# avr-isp-pdi-adapter.net
KiCad netlist of a schematic drawn in EAGLE
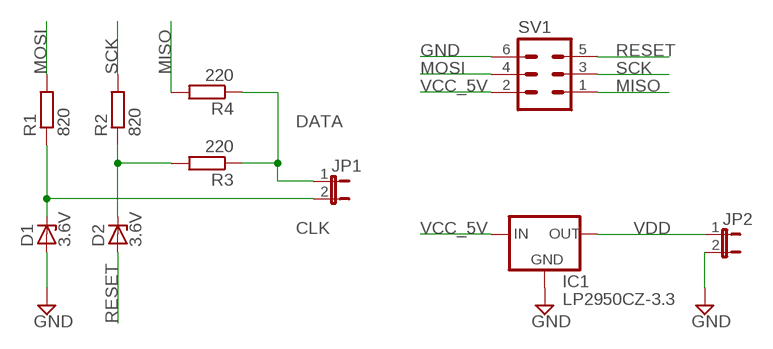
[diagram p0: schematic, sheet 1]

(export (version "E")
  (design (tool "Eeschema 10.0.6"))
  (components
    (comp (ref "D1")
      (value "3.6V")
      (footprint "eagle-import:DO34Z7")
      (libsource (lib "eagle-import") (part "ZENER-DIODEDO34-7"))
    )
    (comp (ref "D2")
      (value "3.6V")
      (footprint "eagle-import:DO34Z7")
      (libsource (lib "eagle-import") (part "ZENER-DIODEDO34-7"))
    )
    (comp (ref "IC1")
      (value "LP2950CZ-3.3")
      (footprint "eagle-import:TO92")
      (libsource (lib "eagle-import") (part "LP2950?CZ-3.3"))
    )
    (comp (ref "JP1")
      (value "JP1E")
      (footprint "eagle-import:JP1")
      (libsource (lib "eagle-import") (part "JP1E"))
    )
    (comp (ref "JP2")
      (value "JP1E")
      (footprint "eagle-import:JP1")
      (libsource (lib "eagle-import") (part "JP1E"))
    )
    (comp (ref "R1")
      (value "820")
      (footprint "eagle-import:0207_10")
      (libsource (lib "eagle-import") (part "R-EU_0207/10"))
    )
    (comp (ref "R2")
      (value "820")
      (footprint "eagle-import:0207_10")
      (libsource (lib "eagle-import") (part "R-EU_0207/10"))
    )
    (comp (ref "R3")
      (value "220")
      (footprint "eagle-import:0207_10")
      (libsource (lib "eagle-import") (part "R-EU_0207/10"))
    )
    (comp (ref "R4")
      (value "220")
      (footprint "eagle-import:0207_10")
      (libsource (lib "eagle-import") (part "R-EU_0207/10"))
    )
    (comp (ref "SV1")
      (value "MA03-2")
      (footprint "eagle-import:MA03-2")
      (libsource (lib "eagle-import") (part "MA03-2"))
    )
  )
  (nets
    (net (code "1") (name "/CLK") (class "Default")
      (node (ref "D1") (pin "C") (pinfunction "C_C") (pintype "passive"))
      (node (ref "JP1") (pin "2") (pinfunction "2_2") (pintype "passive"))
      (node (ref "R1") (pin "1") (pinfunction "1_1") (pintype "passive"))
    )
    (net (code "2") (name "/DATA") (class "Default")
      (node (ref "JP1") (pin "1") (pinfunction "1_1") (pintype "passive"))
      (node (ref "R3") (pin "1") (pinfunction "1_1") (pintype "passive"))
      (node (ref "R4") (pin "1") (pinfunction "1_1") (pintype "passive"))
    )
    (net (code "3") (name "/MISO") (class "Default")
      (node (ref "R4") (pin "2") (pinfunction "2_2") (pintype "passive"))
      (node (ref "SV1") (pin "1") (pinfunction "1_1") (pintype "passive"))
    )
    (net (code "4") (name "/MOSI") (class "Default")
      (node (ref "R1") (pin "2") (pinfunction "2_2") (pintype "passive"))
      (node (ref "SV1") (pin "4") (pinfunction "4_4") (pintype "passive"))
    )
    (net (code "5") (name "/RESET") (class "Default")
      (node (ref "D2") (pin "A") (pinfunction "A_A") (pintype "passive"))
      (node (ref "SV1") (pin "5") (pinfunction "5_5") (pintype "passive"))
    )
    (net (code "6") (name "/SCK") (class "Default")
      (node (ref "R2") (pin "2") (pinfunction "2_2") (pintype "passive"))
      (node (ref "SV1") (pin "3") (pinfunction "3_3") (pintype "passive"))
    )
    (net (code "7") (name "/VCC_5V") (class "Default")
      (node (ref "IC1") (pin "3") (pinfunction "IN_3") (pintype "input"))
      (node (ref "SV1") (pin "2") (pinfunction "2_2") (pintype "passive"))
    )
    (net (code "8") (name "/VDD") (class "Default")
      (node (ref "IC1") (pin "1") (pinfunction "OUT_1") (pintype "passive"))
      (node (ref "JP2") (pin "1") (pinfunction "1_1") (pintype "passive"))
    )
    (net (code "9") (name "GND") (class "Default")
      (node (ref "D1") (pin "A") (pinfunction "A_A") (pintype "passive"))
      (node (ref "IC1") (pin "2") (pinfunction "GND_2") (pintype "input"))
      (node (ref "JP2") (pin "2") (pinfunction "2_2") (pintype "passive"))
      (node (ref "SV1") (pin "6") (pinfunction "6_6") (pintype "passive"))
    )
    (net (code "10") (name "Net-(D2-PadC)") (class "Default")
      (node (ref "D2") (pin "C") (pinfunction "C_C") (pintype "passive"))
      (node (ref "R2") (pin "1") (pinfunction "1_1") (pintype "passive"))
      (node (ref "R3") (pin "2") (pinfunction "2_2") (pintype "passive"))
    )
  )
)
